# shieldHub.net
KiCad netlist of a schematic drawn in EAGLE
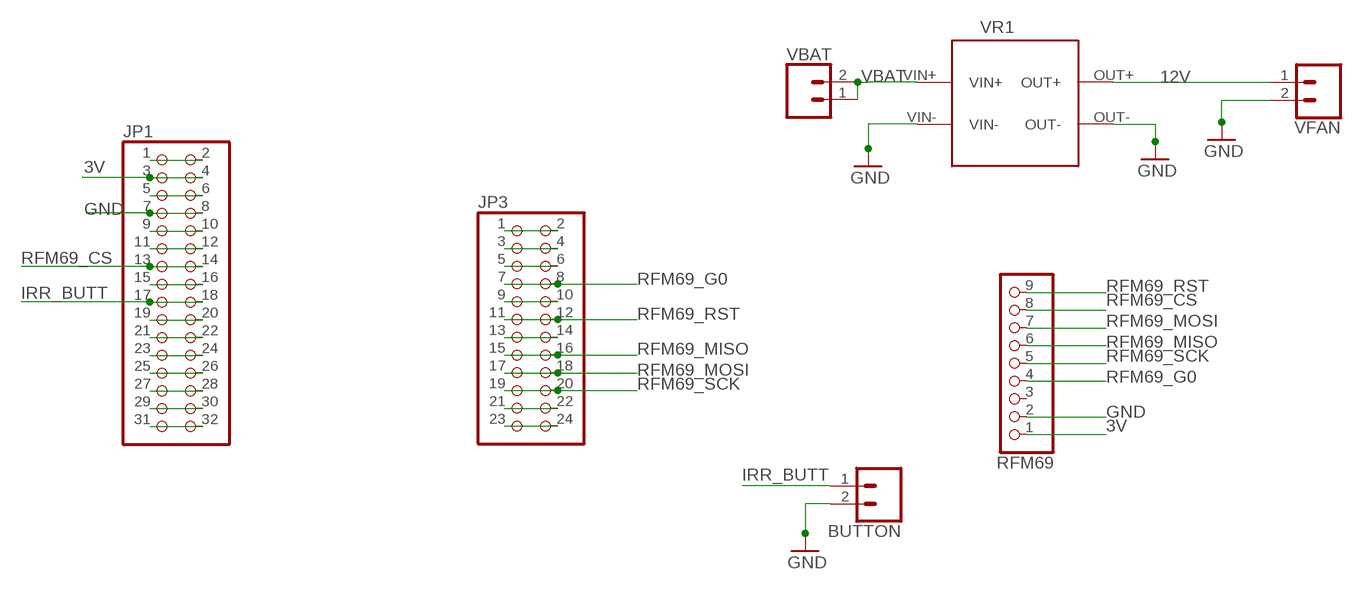
[diagram p0: schematic, sheet 1]

(export (version "E")
  (design (tool "Eeschema 10.0.6"))
  (components
    (comp (ref "BUTTON")
      (value "CONN_023.5MM_LOCK")
      (footprint "eagle-import:SCREWTERMINAL-3.5MM-2_LOCK")
      (libsource (lib "eagle-import") (part "CONN_023.5MM_LOCK"))
    )
    (comp (ref "JP1")
      (value "PINHD-2X16")
      (footprint "eagle-import:2X16")
      (libsource (lib "eagle-import") (part "PINHD-2X16"))
    )
    (comp (ref "JP3")
      (value "PINHD-2X12")
      (footprint "eagle-import:2X12")
      (libsource (lib "eagle-import") (part "PINHD-2X12"))
    )
    (comp (ref "RFM69")
      (value "PINHD-1X9")
      (footprint "eagle-import:1X09-BIG")
      (libsource (lib "eagle-import") (part "PINHD-1X9"))
    )
    (comp (ref "VBAT")
      (value "CONN_02")
      (footprint "eagle-import:1X02")
      (libsource (lib "eagle-import") (part "CONN_02"))
    )
    (comp (ref "VFAN")
      (value "CONN_023.5MM_LOCK")
      (footprint "eagle-import:SCREWTERMINAL-3.5MM-2_LOCK")
      (libsource (lib "eagle-import") (part "CONN_023.5MM_LOCK"))
    )
    (comp (ref "VR1")
      (value "MT3608THROUGH_HOLE")
      (footprint "eagle-import:MT3608")
      (libsource (lib "eagle-import") (part "MT3608THROUGH_HOLE"))
    )
  )
  (nets
    (net (code "1") (name "/3V") (class "Default")
      (node (ref "JP1") (pin "3") (pinfunction "3_3") (pintype "passive"))
      (node (ref "JP1") (pin "4") (pinfunction "4_4") (pintype "passive"))
      (node (ref "RFM69") (pin "1") (pinfunction "1_1") (pintype "passive"))
    )
    (net (code "2") (name "/12V") (class "Default")
      (node (ref "VFAN") (pin "1") (pinfunction "1_1") (pintype "passive"))
      (node (ref "VR1") (pin "OUT+") (pinfunction "OUT+_OUT+") (pintype "power_in"))
    )
    (net (code "3") (name "/IRR_BUTT") (class "Default")
      (node (ref "BUTTON") (pin "1") (pinfunction "1_1") (pintype "passive"))
      (node (ref "JP1") (pin "17") (pinfunction "17_17") (pintype "passive"))
      (node (ref "JP1") (pin "18") (pinfunction "18_18") (pintype "passive"))
    )
    (net (code "4") (name "/RFM69_CS") (class "Default")
      (node (ref "JP1") (pin "13") (pinfunction "13_13") (pintype "passive"))
      (node (ref "JP1") (pin "14") (pinfunction "14_14") (pintype "passive"))
      (node (ref "RFM69") (pin "8") (pinfunction "8_8") (pintype "passive"))
    )
    (net (code "5") (name "/RFM69_G0") (class "Default")
      (node (ref "JP3") (pin "7") (pinfunction "7_7") (pintype "passive"))
      (node (ref "JP3") (pin "8") (pinfunction "8_8") (pintype "passive"))
      (node (ref "RFM69") (pin "4") (pinfunction "4_4") (pintype "passive"))
    )
    (net (code "6") (name "/RFM69_MISO") (class "Default")
      (node (ref "JP3") (pin "15") (pinfunction "15_15") (pintype "passive"))
      (node (ref "JP3") (pin "16") (pinfunction "16_16") (pintype "passive"))
      (node (ref "RFM69") (pin "6") (pinfunction "6_6") (pintype "passive"))
    )
    (net (code "7") (name "/RFM69_MOSI") (class "Default")
      (node (ref "JP3") (pin "17") (pinfunction "17_17") (pintype "passive"))
      (node (ref "JP3") (pin "18") (pinfunction "18_18") (pintype "passive"))
      (node (ref "RFM69") (pin "7") (pinfunction "7_7") (pintype "passive"))
    )
    (net (code "8") (name "/RFM69_RST") (class "Default")
      (node (ref "JP3") (pin "11") (pinfunction "11_11") (pintype "passive"))
      (node (ref "JP3") (pin "12") (pinfunction "12_12") (pintype "passive"))
      (node (ref "RFM69") (pin "9") (pinfunction "9_9") (pintype "passive"))
    )
    (net (code "9") (name "/RFM69_SCK") (class "Default")
      (node (ref "JP3") (pin "19") (pinfunction "19_19") (pintype "passive"))
      (node (ref "JP3") (pin "20") (pinfunction "20_20") (pintype "passive"))
      (node (ref "RFM69") (pin "5") (pinfunction "5_5") (pintype "passive"))
    )
    (net (code "10") (name "/VBAT") (class "Default")
      (node (ref "VBAT") (pin "1") (pinfunction "1_1") (pintype "passive"))
      (node (ref "VBAT") (pin "2") (pinfunction "2_2") (pintype "passive"))
      (node (ref "VR1") (pin "VIN+") (pinfunction "VIN+_VIN+") (pintype "power_in"))
    )
    (net (code "11") (name "GND") (class "Default")
      (node (ref "BUTTON") (pin "2") (pinfunction "2_2") (pintype "passive"))
      (node (ref "JP1") (pin "7") (pinfunction "7_7") (pintype "passive"))
      (node (ref "JP1") (pin "8") (pinfunction "8_8") (pintype "passive"))
      (node (ref "RFM69") (pin "2") (pinfunction "2_2") (pintype "passive"))
      (node (ref "VFAN") (pin "2") (pinfunction "2_2") (pintype "passive"))
      (node (ref "VR1") (pin "OUT-") (pinfunction "OUT-_OUT-") (pintype "power_in"))
      (node (ref "VR1") (pin "VIN-") (pinfunction "VIN-_VIN-") (pintype "power_in"))
    )
    (net (code "12") (name "Net-(JP1-Pad1)") (class "Default")
      (node (ref "JP1") (pin "1") (pinfunction "1_1") (pintype "passive"))
      (node (ref "JP1") (pin "2") (pinfunction "2_2") (pintype "passive"))
    )
    (net (code "13") (name "Net-(JP1-Pad5)") (class "Default")
      (node (ref "JP1") (pin "5") (pinfunction "5_5") (pintype "passive"))
      (node (ref "JP1") (pin "6") (pinfunction "6_6") (pintype "passive"))
    )
    (net (code "14") (name "Net-(JP1-Pad10)") (class "Default")
      (node (ref "JP1") (pin "10") (pinfunction "10_10") (pintype "passive"))
      (node (ref "JP1") (pin "9") (pinfunction "9_9") (pintype "passive"))
    )
    (net (code "15") (name "Net-(JP1-Pad11)") (class "Default")
      (node (ref "JP1") (pin "11") (pinfunction "11_11") (pintype "passive"))
      (node (ref "JP1") (pin "12") (pinfunction "12_12") (pintype "passive"))
    )
    (net (code "16") (name "Net-(JP1-Pad15)") (class "Default")
      (node (ref "JP1") (pin "15") (pinfunction "15_15") (pintype "passive"))
      (node (ref "JP1") (pin "16") (pinfunction "16_16") (pintype "passive"))
    )
    (net (code "17") (name "Net-(JP1-Pad19)") (class "Default")
      (node (ref "JP1") (pin "19") (pinfunction "19_19") (pintype "passive"))
      (node (ref "JP1") (pin "20") (pinfunction "20_20") (pintype "passive"))
    )
    (net (code "18") (name "Net-(JP1-Pad21)") (class "Default")
      (node (ref "JP1") (pin "21") (pinfunction "21_21") (pintype "passive"))
      (node (ref "JP1") (pin "22") (pinfunction "22_22") (pintype "passive"))
    )
    (net (code "19") (name "Net-(JP1-Pad23)") (class "Default")
      (node (ref "JP1") (pin "23") (pinfunction "23_23") (pintype "passive"))
      (node (ref "JP1") (pin "24") (pinfunction "24_24") (pintype "passive"))
    )
    (net (code "20") (name "Net-(JP1-Pad25)") (class "Default")
      (node (ref "JP1") (pin "25") (pinfunction "25_25") (pintype "passive"))
      (node (ref "JP1") (pin "26") (pinfunction "26_26") (pintype "passive"))
    )
    (net (code "21") (name "Net-(JP1-Pad27)") (class "Default")
      (node (ref "JP1") (pin "27") (pinfunction "27_27") (pintype "passive"))
      (node (ref "JP1") (pin "28") (pinfunction "28_28") (pintype "passive"))
    )
    (net (code "22") (name "Net-(JP1-Pad29)") (class "Default")
      (node (ref "JP1") (pin "29") (pinfunction "29_29") (pintype "passive"))
      (node (ref "JP1") (pin "30") (pinfunction "30_30") (pintype "passive"))
    )
    (net (code "23") (name "Net-(JP1-Pad31)") (class "Default")
      (node (ref "JP1") (pin "31") (pinfunction "31_31") (pintype "passive"))
      (node (ref "JP1") (pin "32") (pinfunction "32_32") (pintype "passive"))
    )
    (net (code "24") (name "Net-(JP3-Pad1)") (class "Default")
      (node (ref "JP3") (pin "1") (pinfunction "1_1") (pintype "passive"))
      (node (ref "JP3") (pin "2") (pinfunction "2_2") (pintype "passive"))
    )
    (net (code "25") (name "Net-(JP3-Pad3)") (class "Default")
      (node (ref "JP3") (pin "3") (pinfunction "3_3") (pintype "passive"))
      (node (ref "JP3") (pin "4") (pinfunction "4_4") (pintype "passive"))
    )
    (net (code "26") (name "Net-(JP3-Pad5)") (class "Default")
      (node (ref "JP3") (pin "5") (pinfunction "5_5") (pintype "passive"))
      (node (ref "JP3") (pin "6") (pinfunction "6_6") (pintype "passive"))
    )
    (net (code "27") (name "Net-(JP3-Pad10)") (class "Default")
      (node (ref "JP3") (pin "10") (pinfunction "10_10") (pintype "passive"))
      (node (ref "JP3") (pin "9") (pinfunction "9_9") (pintype "passive"))
    )
    (net (code "28") (name "Net-(JP3-Pad13)") (class "Default")
      (node (ref "JP3") (pin "13") (pinfunction "13_13") (pintype "passive"))
      (node (ref "JP3") (pin "14") (pinfunction "14_14") (pintype "passive"))
    )
    (net (code "29") (name "Net-(JP3-Pad21)") (class "Default")
      (node (ref "JP3") (pin "21") (pinfunction "21_21") (pintype "passive"))
      (node (ref "JP3") (pin "22") (pinfunction "22_22") (pintype "passive"))
    )
    (net (code "30") (name "Net-(JP3-Pad23)") (class "Default")
      (node (ref "JP3") (pin "23") (pinfunction "23_23") (pintype "passive"))
      (node (ref "JP3") (pin "24") (pinfunction "24_24") (pintype "passive"))
    )
    (net (code "31") (name "unconnected-(RFM69-Pad3)") (class "Default")
      (node (ref "RFM69") (pin "3") (pinfunction "3_3") (pintype "passive"))
    )
  )
)
